# EntradasAnalogicas.net
KiCad netlist of a schematic drawn in Altium Designer
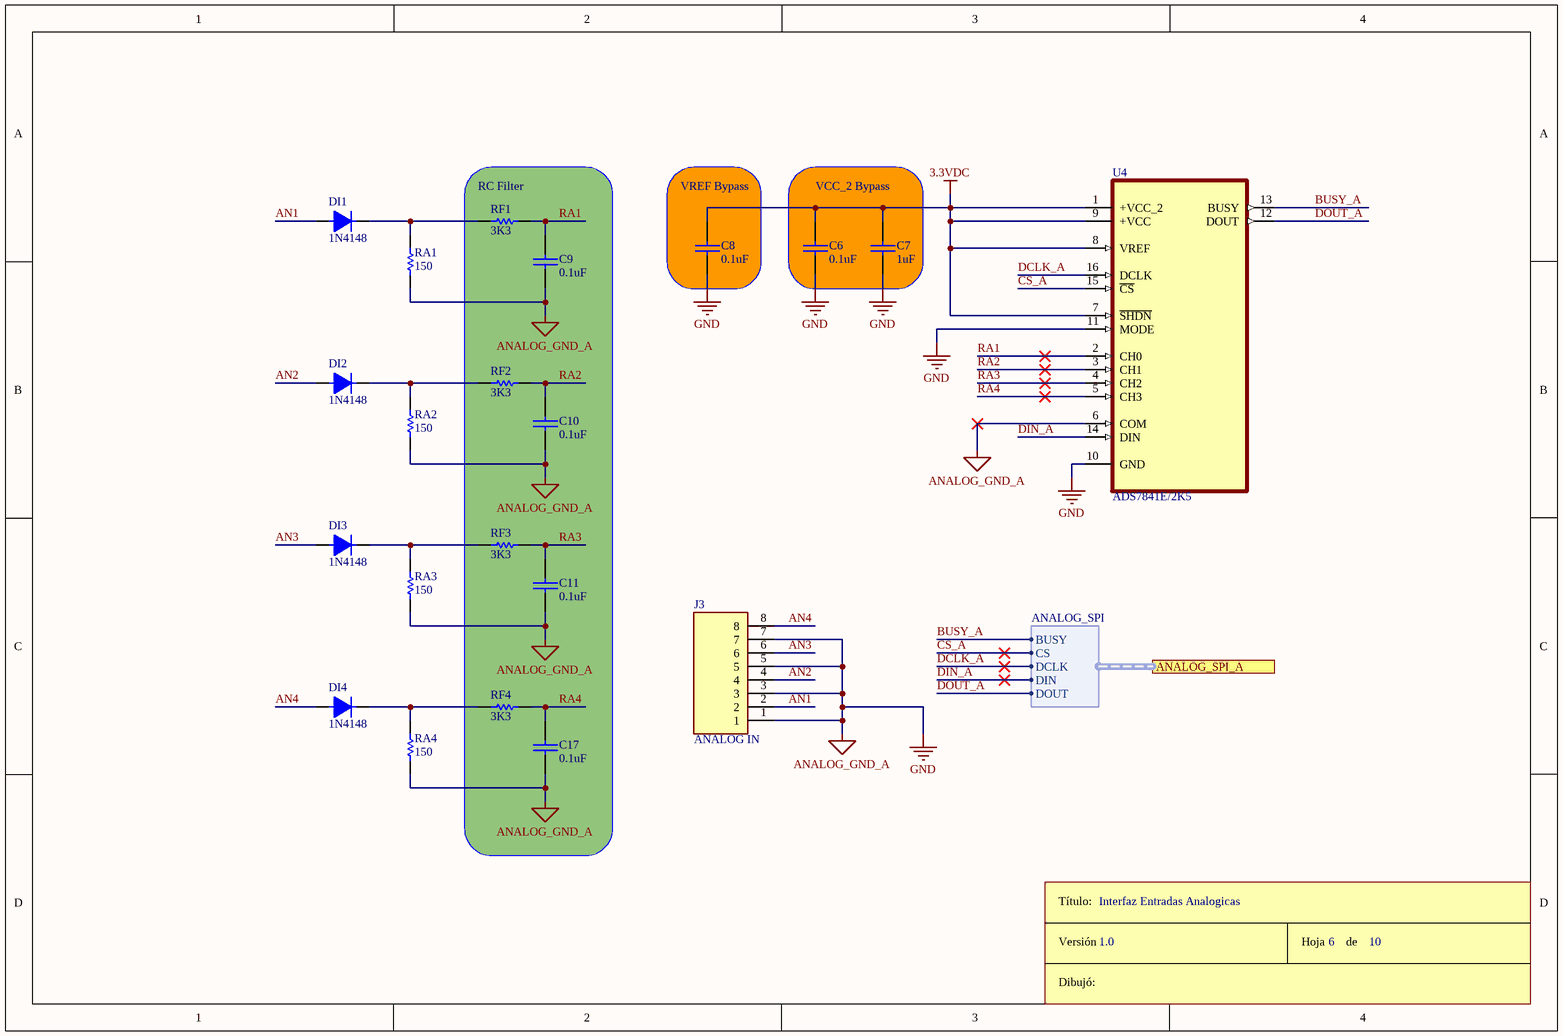
[diagram p0: EntradasAnalogicas.SchDoc]

(export (version "E")
  (design (tool "Eeschema 10.0.6"))
  (components
    (comp (ref "C6") (value "0.1uF") (footprint "CAP100") (libsource (lib "LIBEBAL") (part "CAP")))
    (comp (ref "C7") (value "1uF") (footprint "CAP200") (libsource (lib "LIBEBAL") (part "CAP")))
    (comp (ref "C8") (value "0.1uF") (footprint "CAP100") (libsource (lib "LIBEBAL") (part "CAP")))
    (comp (ref "C9") (value "0.1uF") (footprint "CAP100") (libsource (lib "LIBEBAL") (part "CAP")))
    (comp (ref "C10") (value "0.1uF") (footprint "CAP100") (libsource (lib "LIBEBAL") (part "CAP")))
    (comp (ref "C11") (value "0.1uF") (footprint "CAP100") (libsource (lib "LIBEBAL") (part "CAP")))
    (comp (ref "C17") (value "0.1uF") (footprint "CAP100") (libsource (lib "LIBEBAL") (part "CAP")))
    (comp (ref "DI1") (value "1N4148") (footprint "DO41") (libsource (lib "LIBEBAL") (part "DIODO")))
    (comp (ref "DI2") (value "1N4148") (footprint "DO41") (libsource (lib "LIBEBAL") (part "DIODO")))
    (comp (ref "DI3") (value "1N4148") (footprint "DO41") (libsource (lib "LIBEBAL") (part "DIODO")))
    (comp (ref "DI4") (value "1N4148") (footprint "DO41") (libsource (lib "LIBEBAL") (part "DIODO")))
    (comp (ref "J3")
      (value "ANALOG IN")
      (footprint "TE_1586863-8")
      (description "Conn Power HDR 8 POS 4.2mm Solder RA Thru-Hole 8 Terminal 1 Port Tray")
      (fields (field (name "MF") "TE Connectivity") (field (name "MP") "1586863-8"))
      (libsource (lib "MFW8R") (part "1586863-8"))
    )
    (comp (ref "RA1") (value "150") (footprint "RES300") (libsource (lib "LIBEBAL") (part "RES")))
    (comp (ref "RA2") (value "150") (footprint "RES300") (libsource (lib "LIBEBAL") (part "RES")))
    (comp (ref "RA3") (value "150") (footprint "RES300") (libsource (lib "LIBEBAL") (part "RES")))
    (comp (ref "RA4") (value "150") (footprint "RES300") (libsource (lib "LIBEBAL") (part "RES")))
    (comp (ref "RF1") (value "3K3") (footprint "RES300") (libsource (lib "LIBEBAL") (part "RES")))
    (comp (ref "RF2") (value "3K3") (footprint "RES300") (libsource (lib "LIBEBAL") (part "RES")))
    (comp (ref "RF3") (value "3K3") (footprint "RES300") (libsource (lib "LIBEBAL") (part "RES")))
    (comp (ref "RF4") (value "3K3") (footprint "RES300") (libsource (lib "LIBEBAL") (part "RES")))
    (comp (ref "ROT4") (value "Rótulo") (libsource (lib "LIB PIO IX") (part "Rótulo")))
    (comp (ref "U4")
      (value "ADS7841E/2K5")
      (footprint "SOP63P600X175-16N")
      (description "ANALOG-TO-DIGITAL CONVERTER")
      (libsource (lib "ADS7841E_2K5_Rev2") (part "ADS7841E/2K5"))
    )
  )
  (nets
    (net (code "2") (name "/AN1") (class "Default")
      (node (ref "DI1") (pin "1") (pinfunction "1_1") (pintype "passive"))
      (node (ref "J3") (pin "2") (pinfunction "2_2") (pintype "passive"))
    )
    (net (code "3") (name "/AN2") (class "Default")
      (node (ref "DI2") (pin "1") (pinfunction "1_1") (pintype "passive"))
      (node (ref "J3") (pin "4") (pinfunction "4_4") (pintype "passive"))
    )
    (net (code "4") (name "/AN3") (class "Default")
      (node (ref "DI3") (pin "1") (pinfunction "1_1") (pintype "passive"))
      (node (ref "J3") (pin "6") (pinfunction "6_6") (pintype "passive"))
    )
    (net (code "5") (name "/AN4") (class "Default")
      (node (ref "DI4") (pin "1") (pinfunction "1_1") (pintype "passive"))
      (node (ref "J3") (pin "8") (pinfunction "8_8") (pintype "passive"))
    )
    (net (code "6") (name "/BUSY_A") (class "Default")
      (node (ref "U4") (pin "13") (pinfunction "BUSY_13") (pintype "output"))
    )
    (net (code "7") (name "/CS_A") (class "Default")
      (node (ref "U4") (pin "15") (pinfunction "~{CS}_15") (pintype "input"))
    )
    (net (code "8") (name "/DCLK_A") (class "Default")
      (node (ref "U4") (pin "16") (pinfunction "DCLK_16") (pintype "input"))
    )
    (net (code "9") (name "/DIN_A") (class "Default")
      (node (ref "U4") (pin "14") (pinfunction "DIN_14") (pintype "input"))
    )
    (net (code "10") (name "/DOUT_A") (class "Default")
      (node (ref "U4") (pin "12") (pinfunction "DOUT_12") (pintype "output"))
    )
    (net (code "11") (name "/RA1") (class "Default")
      (node (ref "C9") (pin "1") (pinfunction "1_1") (pintype "passive"))
      (node (ref "RF1") (pin "2") (pinfunction "2_2") (pintype "passive"))
      (node (ref "U4") (pin "2") (pinfunction "CH0_2") (pintype "input"))
    )
    (net (code "12") (name "/RA2") (class "Default")
      (node (ref "C10") (pin "1") (pinfunction "1_1") (pintype "passive"))
      (node (ref "RF2") (pin "2") (pinfunction "2_2") (pintype "passive"))
      (node (ref "U4") (pin "3") (pinfunction "CH1_3") (pintype "input"))
    )
    (net (code "13") (name "/RA3") (class "Default")
      (node (ref "C11") (pin "1") (pinfunction "1_1") (pintype "passive"))
      (node (ref "RF3") (pin "2") (pinfunction "2_2") (pintype "passive"))
      (node (ref "U4") (pin "4") (pinfunction "CH2_4") (pintype "input"))
    )
    (net (code "14") (name "/RA4") (class "Default")
      (node (ref "C17") (pin "1") (pinfunction "1_1") (pintype "passive"))
      (node (ref "RF4") (pin "2") (pinfunction "2_2") (pintype "passive"))
      (node (ref "U4") (pin "5") (pinfunction "CH3_5") (pintype "input"))
    )
    (net (code "16") (name "3.3VDC") (class "Default")
      (node (ref "C6") (pin "1") (pinfunction "1_1") (pintype "passive"))
      (node (ref "C7") (pin "1") (pinfunction "1_1") (pintype "passive"))
      (node (ref "C8") (pin "1") (pinfunction "1_1") (pintype "passive"))
      (node (ref "U4") (pin "1") (pinfunction "+VCC_2_1") (pintype "power_in"))
      (node (ref "U4") (pin "7") (pinfunction "~{SHDN}_7") (pintype "input"))
      (node (ref "U4") (pin "8") (pinfunction "VREF_8") (pintype "input"))
      (node (ref "U4") (pin "9") (pinfunction "+VCC_9") (pintype "power_in"))
    )
    (net (code "17") (name "ANALOG_GND_A") (class "Default")
      (node (ref "C10") (pin "2") (pinfunction "2_2") (pintype "passive"))
      (node (ref "C11") (pin "2") (pinfunction "2_2") (pintype "passive"))
      (node (ref "C17") (pin "2") (pinfunction "2_2") (pintype "passive"))
      (node (ref "C6") (pin "2") (pinfunction "2_2") (pintype "passive"))
      (node (ref "C7") (pin "2") (pinfunction "2_2") (pintype "passive"))
      (node (ref "C8") (pin "2") (pinfunction "2_2") (pintype "passive"))
      (node (ref "C9") (pin "2") (pinfunction "2_2") (pintype "passive"))
      (node (ref "J3") (pin "1") (pinfunction "1_1") (pintype "passive"))
      (node (ref "J3") (pin "3") (pinfunction "3_3") (pintype "passive"))
      (node (ref "J3") (pin "5") (pinfunction "5_5") (pintype "passive"))
      (node (ref "J3") (pin "7") (pinfunction "7_7") (pintype "passive"))
      (node (ref "RA1") (pin "1") (pinfunction "1_1") (pintype "passive"))
      (node (ref "RA2") (pin "1") (pinfunction "1_1") (pintype "passive"))
      (node (ref "RA3") (pin "1") (pinfunction "1_1") (pintype "passive"))
      (node (ref "RA4") (pin "1") (pinfunction "1_1") (pintype "passive"))
      (node (ref "U4") (pin "10") (pinfunction "GND_10") (pintype "passive"))
      (node (ref "U4") (pin "11") (pinfunction "MODE_11") (pintype "input"))
      (node (ref "U4") (pin "6") (pinfunction "COM_6") (pintype "input"))
    )
    (net (code "18") (name "Net-(DI1-Pad2)") (class "Default")
      (node (ref "DI1") (pin "2") (pinfunction "2_2") (pintype "passive"))
      (node (ref "RA1") (pin "2") (pinfunction "2_2") (pintype "passive"))
      (node (ref "RF1") (pin "1") (pinfunction "1_1") (pintype "passive"))
    )
    (net (code "19") (name "Net-(DI2-Pad2)") (class "Default")
      (node (ref "DI2") (pin "2") (pinfunction "2_2") (pintype "passive"))
      (node (ref "RA2") (pin "2") (pinfunction "2_2") (pintype "passive"))
      (node (ref "RF2") (pin "1") (pinfunction "1_1") (pintype "passive"))
    )
    (net (code "20") (name "Net-(DI3-Pad2)") (class "Default")
      (node (ref "DI3") (pin "2") (pinfunction "2_2") (pintype "passive"))
      (node (ref "RA3") (pin "2") (pinfunction "2_2") (pintype "passive"))
      (node (ref "RF3") (pin "1") (pinfunction "1_1") (pintype "passive"))
    )
    (net (code "21") (name "Net-(DI4-Pad2)") (class "Default")
      (node (ref "DI4") (pin "2") (pinfunction "2_2") (pintype "passive"))
      (node (ref "RA4") (pin "2") (pinfunction "2_2") (pintype "passive"))
      (node (ref "RF4") (pin "1") (pinfunction "1_1") (pintype "passive"))
    )
  )
)
